# main.net
KiCad netlist of a schematic drawn in EAGLE
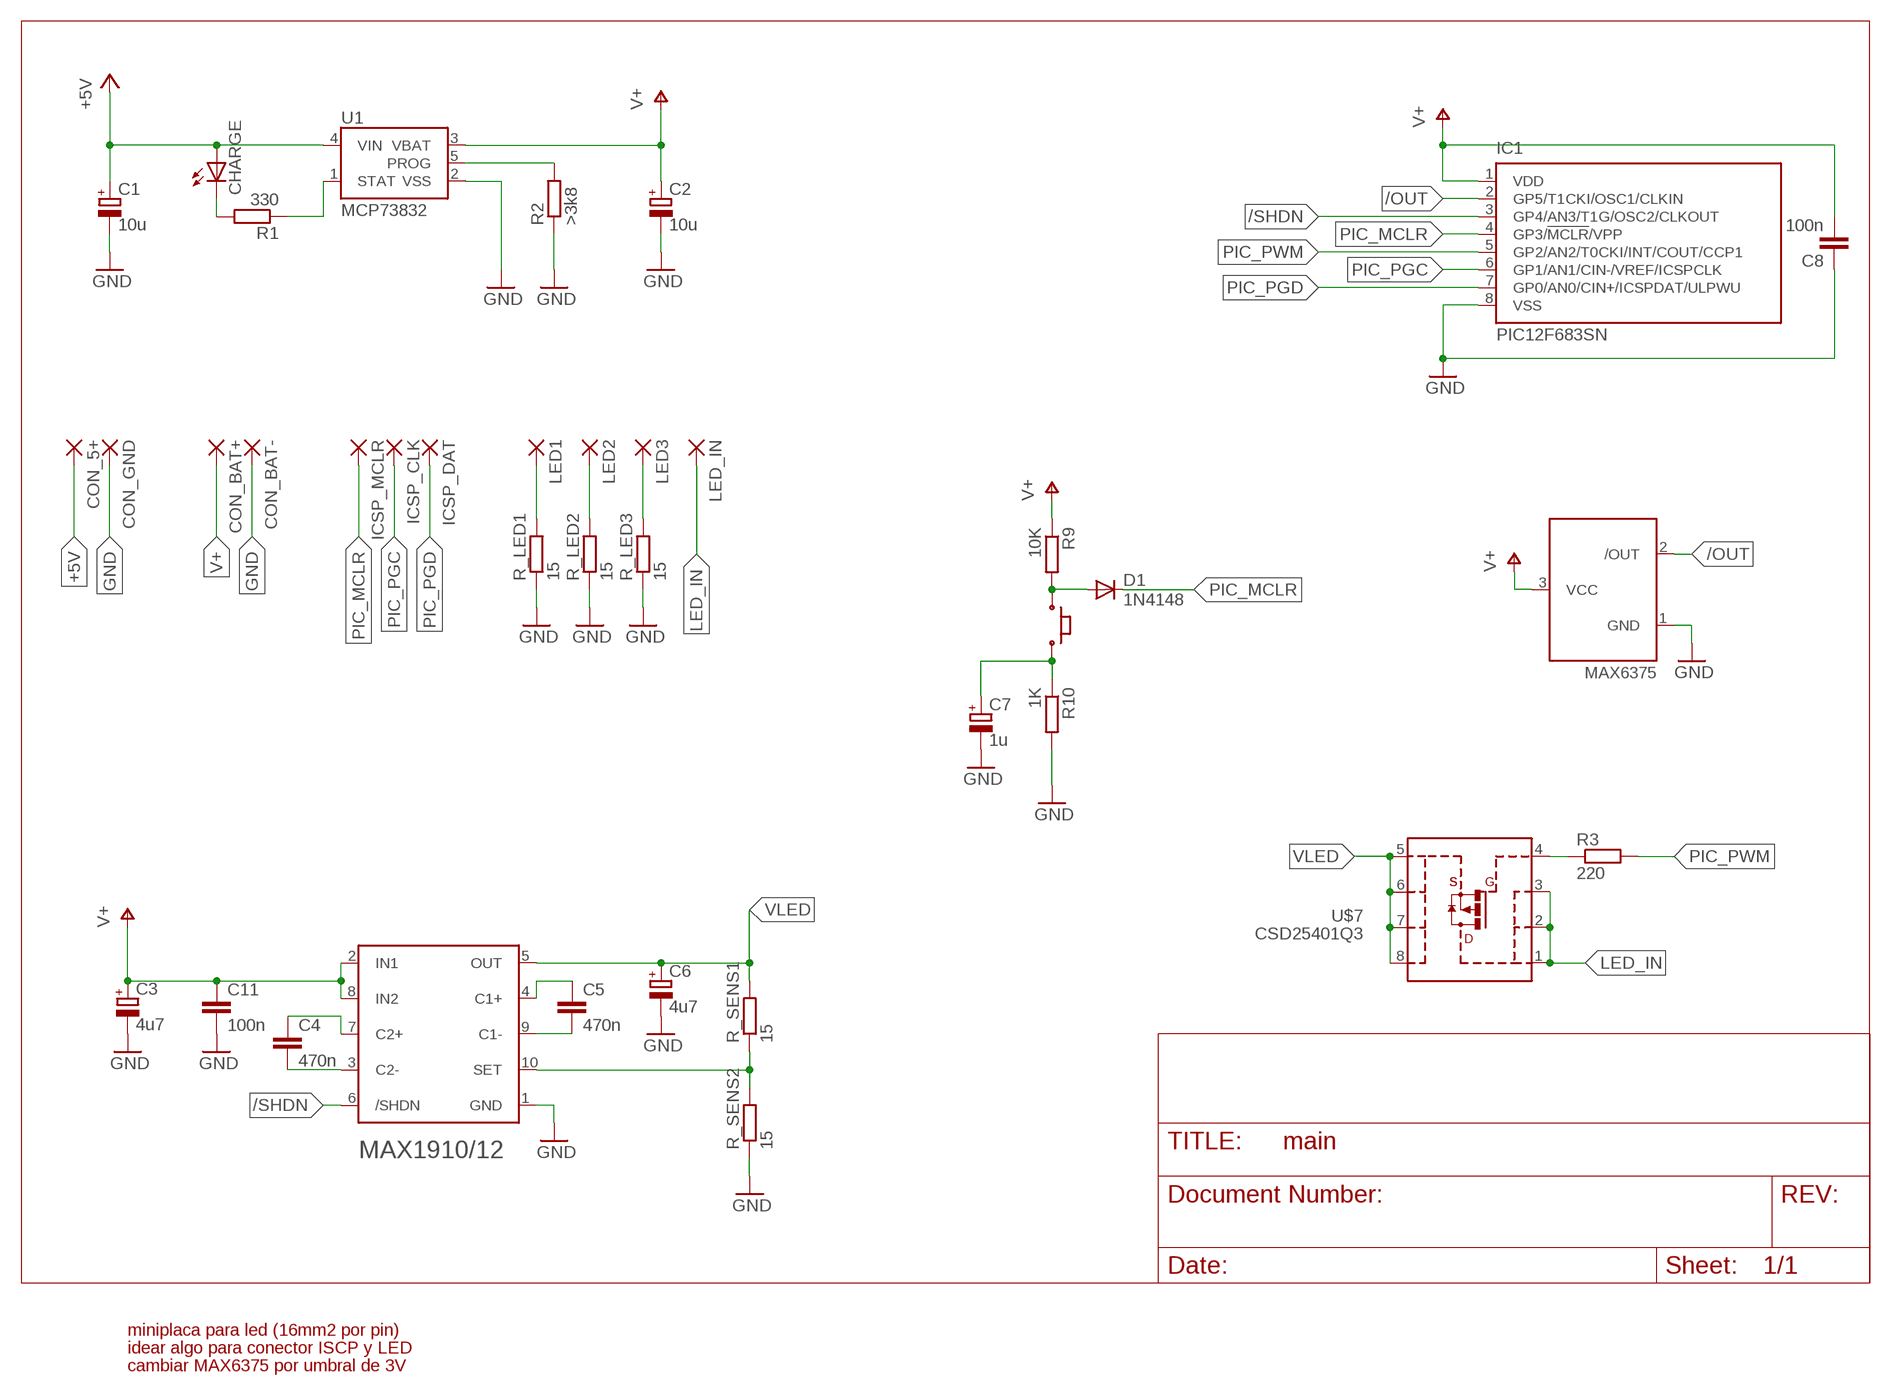
[diagram p0: schematic, sheet 1]

(export (version "E")
  (design (tool "Eeschema 10.0.6"))
  (components
    (comp (ref "C1")
      (value "10u")
      (footprint "eagle-import:SMC_A")
      (libsource (lib "eagle-import") (part "CPOL-EUSMCA"))
    )
    (comp (ref "C2")
      (value "10u")
      (footprint "eagle-import:SMC_A")
      (libsource (lib "eagle-import") (part "CPOL-EUSMCA"))
    )
    (comp (ref "C3")
      (value "4u7")
      (footprint "eagle-import:SMC_A")
      (libsource (lib "eagle-import") (part "CPOL-EUSMCA"))
    )
    (comp (ref "C4")
      (value "470n")
      (footprint "eagle-import:C1206")
      (libsource (lib "eagle-import") (part "C-EUC1206"))
    )
    (comp (ref "C5")
      (value "470n")
      (footprint "eagle-import:C1206")
      (libsource (lib "eagle-import") (part "C-EUC1206"))
    )
    (comp (ref "C6")
      (value "4u7")
      (footprint "eagle-import:SMC_A")
      (libsource (lib "eagle-import") (part "CPOL-EUSMCA"))
    )
    (comp (ref "C7")
      (value "1u")
      (footprint "eagle-import:SMC_A")
      (libsource (lib "eagle-import") (part "CPOL-EUSMCA"))
    )
    (comp (ref "C8")
      (value "100n")
      (footprint "eagle-import:C1206")
      (libsource (lib "eagle-import") (part "C-EUC1206"))
    )
    (comp (ref "C11")
      (value "100n")
      (footprint "eagle-import:C1206")
      (libsource (lib "eagle-import") (part "C-EUC1206"))
    )
    (comp (ref "CHARGE")
      (value "LEDCHIPLED_1206")
      (footprint "eagle-import:CHIPLED_1206")
      (libsource (lib "eagle-import") (part "LEDCHIPLED_1206"))
    )
    (comp (ref "CON_5+")
      (value "SMD5")
      (footprint "eagle-import:SMD2,54-5,08")
      (libsource (lib "eagle-import") (part "SMD5"))
    )
    (comp (ref "CON_BAT+")
      (value "SMD5")
      (footprint "eagle-import:SMD2,54-5,08")
      (libsource (lib "eagle-import") (part "SMD5"))
    )
    (comp (ref "CON_BAT-")
      (value "SMD5")
      (footprint "eagle-import:SMD2,54-5,08")
      (libsource (lib "eagle-import") (part "SMD5"))
    )
    (comp (ref "CON_GND")
      (value "SMD5")
      (footprint "eagle-import:SMD2,54-5,08")
      (libsource (lib "eagle-import") (part "SMD5"))
    )
    (comp (ref "D1")
      (value "1N4148")
      (footprint "eagle-import:SOD80")
      (libsource (lib "eagle-import") (part "1N4148"))
    )
    (comp (ref "IC1")
      (value "PIC12F683SN")
      (footprint "eagle-import:SO-08")
      (fields (field (name "MF") "MICROCHIP") (field (name "MPN") "PIC12F683-I/SN"))
      (libsource (lib "eagle-import") (part "PIC12F683SN"))
    )
    (comp (ref "ICSP_CLK")
      (value "SMD5")
      (footprint "eagle-import:SMD2,54-5,08")
      (libsource (lib "eagle-import") (part "SMD5"))
    )
    (comp (ref "ICSP_DAT")
      (value "SMD5")
      (footprint "eagle-import:SMD2,54-5,08")
      (libsource (lib "eagle-import") (part "SMD5"))
    )
    (comp (ref "ICSP_MCLR")
      (value "SMD5")
      (footprint "eagle-import:SMD2,54-5,08")
      (libsource (lib "eagle-import") (part "SMD5"))
    )
    (comp (ref "LED1")
      (value "SMD5")
      (footprint "eagle-import:SMD2,54-5,08")
      (libsource (lib "eagle-import") (part "SMD5"))
    )
    (comp (ref "LED2")
      (value "SMD5")
      (footprint "eagle-import:SMD2,54-5,08")
      (libsource (lib "eagle-import") (part "SMD5"))
    )
    (comp (ref "LED3")
      (value "SMD5")
      (footprint "eagle-import:SMD2,54-5,08")
      (libsource (lib "eagle-import") (part "SMD5"))
    )
    (comp (ref "LED_IN")
      (value "SMD5")
      (footprint "eagle-import:SMD2,54-5,08")
      (libsource (lib "eagle-import") (part "SMD5"))
    )
    (comp (ref "R1")
      (value "330")
      (footprint "eagle-import:R1206")
      (libsource (lib "eagle-import") (part "R-EU_R1206"))
    )
    (comp (ref "R2")
      (value ">3k8")
      (footprint "eagle-import:R1206")
      (libsource (lib "eagle-import") (part "R-EU_R1206"))
    )
    (comp (ref "R3")
      (value "220")
      (footprint "eagle-import:R1206")
      (libsource (lib "eagle-import") (part "R-EU_R1206"))
    )
    (comp (ref "R9")
      (value "10K")
      (footprint "eagle-import:R1206")
      (libsource (lib "eagle-import") (part "R-EU_R1206"))
    )
    (comp (ref "R10")
      (value "1K")
      (footprint "eagle-import:R1206")
      (libsource (lib "eagle-import") (part "R-EU_R1206"))
    )
    (comp (ref "R_LED1")
      (value "15")
      (footprint "eagle-import:R1206")
      (libsource (lib "eagle-import") (part "R-EU_R1206"))
    )
    (comp (ref "R_LED2")
      (value "15")
      (footprint "eagle-import:R1206")
      (libsource (lib "eagle-import") (part "R-EU_R1206"))
    )
    (comp (ref "R_LED3")
      (value "15")
      (footprint "eagle-import:R1206")
      (libsource (lib "eagle-import") (part "R-EU_R1206"))
    )
    (comp (ref "R_SENS1")
      (value "15")
      (footprint "eagle-import:R1206")
      (libsource (lib "eagle-import") (part "R-EU_R1206"))
    )
    (comp (ref "R_SENS2")
      (value "15")
      (footprint "eagle-import:R1206")
      (libsource (lib "eagle-import") (part "R-EU_R1206"))
    )
    (comp (ref "U$1")
      (value "MAX1910/12")
      (footprint "eagle-import:UMAX_USOP_10L")
      (libsource (lib "eagle-import") (part "MAX1910/12"))
    )
    (comp (ref "U$2")
      (value "MAX6375")
      (footprint "eagle-import:SC70-3-W")
      (libsource (lib "eagle-import") (part "MAX6375"))
    )
    (comp (ref "U$6")
      (value "MICROBUTTONE-MERCHAN")
      (footprint "eagle-import:MICROBUTTON_2")
      (libsource (lib "eagle-import") (part "MICROBUTTONE-MERCHAN"))
    )
    (comp (ref "U$7")
      (value "CSD25401Q3")
      (footprint "eagle-import:SON3X3")
      (libsource (lib "eagle-import") (part "CSD25401Q3"))
    )
    (comp (ref "U1")
      (value "MCP73832")
      (footprint "eagle-import:SOT23-5")
      (libsource (lib "eagle-import") (part "MCP73832"))
    )
  )
  (nets
    (net (code "1") (name "+5V") (class "Default")
      (node (ref "C1") (pin "+") (pinfunction "+_+") (pintype "passive"))
      (node (ref "CHARGE") (pin "A") (pinfunction "A_A") (pintype "passive"))
      (node (ref "CON_5+") (pin "1") (pinfunction "P_1") (pintype "passive"))
      (node (ref "U1") (pin "4") (pinfunction "VIN_4") (pintype "power_in"))
    )
    (net (code "2") (name "GND") (class "Default")
      (node (ref "C1") (pin "-") (pinfunction "-_-") (pintype "passive"))
      (node (ref "C11") (pin "2") (pinfunction "2_2") (pintype "passive"))
      (node (ref "C2") (pin "-") (pinfunction "-_-") (pintype "passive"))
      (node (ref "C3") (pin "-") (pinfunction "-_-") (pintype "passive"))
      (node (ref "C6") (pin "-") (pinfunction "-_-") (pintype "passive"))
      (node (ref "C7") (pin "-") (pinfunction "-_-") (pintype "passive"))
      (node (ref "C8") (pin "1") (pinfunction "1_1") (pintype "passive"))
      (node (ref "CON_BAT-") (pin "1") (pinfunction "P_1") (pintype "passive"))
      (node (ref "CON_GND") (pin "1") (pinfunction "P_1") (pintype "passive"))
      (node (ref "IC1") (pin "8") (pinfunction "VSS_8") (pintype "power_in"))
      (node (ref "R10") (pin "2") (pinfunction "2_2") (pintype "passive"))
      (node (ref "R2") (pin "1") (pinfunction "1_1") (pintype "passive"))
      (node (ref "R_LED1") (pin "1") (pinfunction "1_1") (pintype "passive"))
      (node (ref "R_LED2") (pin "1") (pinfunction "1_1") (pintype "passive"))
      (node (ref "R_LED3") (pin "1") (pinfunction "1_1") (pintype "passive"))
      (node (ref "R_SENS2") (pin "1") (pinfunction "1_1") (pintype "passive"))
      (node (ref "U$1") (pin "1") (pinfunction "GND_1") (pintype "power_in"))
      (node (ref "U$2") (pin "1") (pinfunction "GND_1") (pintype "power_in"))
      (node (ref "U1") (pin "2") (pinfunction "VSS_2") (pintype "power_in"))
    )
    (net (code "3") (name "LED_IN") (class "Default")
      (node (ref "LED_IN") (pin "1") (pinfunction "P_1") (pintype "passive"))
      (node (ref "U$7") (pin "1") (pinfunction "D$1_1") (pintype "bidirectional"))
      (node (ref "U$7") (pin "2") (pinfunction "D$2_2") (pintype "bidirectional"))
      (node (ref "U$7") (pin "3") (pinfunction "D$3_3") (pintype "bidirectional"))
    )
    (net (code "4") (name "Net-(C7-Pad+)") (class "Default")
      (node (ref "C7") (pin "+") (pinfunction "+_+") (pintype "passive"))
      (node (ref "R10") (pin "1") (pinfunction "1_1") (pintype "passive"))
      (node (ref "U$6") (pin "P$2") (pinfunction "P$2_P$2") (pintype "bidirectional"))
    )
    (net (code "5") (name "Net-(CHARGE-PadC)") (class "Default")
      (node (ref "CHARGE") (pin "C") (pinfunction "C_C") (pintype "passive"))
      (node (ref "R1") (pin "2") (pinfunction "2_2") (pintype "passive"))
    )
    (net (code "6") (name "Net-(D1-A)") (class "Default")
      (node (ref "D1") (pin "1") (pinfunction "A_1") (pintype "passive"))
      (node (ref "R9") (pin "2") (pinfunction "2_2") (pintype "passive"))
      (node (ref "U$6") (pin "P$1") (pinfunction "P$1_P$1") (pintype "bidirectional"))
    )
    (net (code "7") (name "Net-(LED1-P)") (class "Default")
      (node (ref "LED1") (pin "1") (pinfunction "P_1") (pintype "passive"))
      (node (ref "R_LED1") (pin "2") (pinfunction "2_2") (pintype "passive"))
    )
    (net (code "8") (name "Net-(LED2-P)") (class "Default")
      (node (ref "LED2") (pin "1") (pinfunction "P_1") (pintype "passive"))
      (node (ref "R_LED2") (pin "2") (pinfunction "2_2") (pintype "passive"))
    )
    (net (code "9") (name "Net-(LED3-P)") (class "Default")
      (node (ref "LED3") (pin "1") (pinfunction "P_1") (pintype "passive"))
      (node (ref "R_LED3") (pin "2") (pinfunction "2_2") (pintype "passive"))
    )
    (net (code "10") (name "Net-(U$1-C1+)") (class "Default")
      (node (ref "C5") (pin "1") (pinfunction "1_1") (pintype "passive"))
      (node (ref "U$1") (pin "4") (pinfunction "C1+_4") (pintype "bidirectional"))
    )
    (net (code "11") (name "Net-(U$1-C1-)") (class "Default")
      (node (ref "C5") (pin "2") (pinfunction "2_2") (pintype "passive"))
      (node (ref "U$1") (pin "9") (pinfunction "C1-_9") (pintype "bidirectional"))
    )
    (net (code "12") (name "Net-(U$1-C2+)") (class "Default")
      (node (ref "C4") (pin "1") (pinfunction "1_1") (pintype "passive"))
      (node (ref "U$1") (pin "7") (pinfunction "C2+_7") (pintype "bidirectional"))
    )
    (net (code "13") (name "Net-(U$1-C2-)") (class "Default")
      (node (ref "C4") (pin "2") (pinfunction "2_2") (pintype "passive"))
      (node (ref "U$1") (pin "3") (pinfunction "C2-_3") (pintype "bidirectional"))
    )
    (net (code "14") (name "Net-(U$1-SET)") (class "Default")
      (node (ref "R_SENS1") (pin "1") (pinfunction "1_1") (pintype "passive"))
      (node (ref "R_SENS2") (pin "2") (pinfunction "2_2") (pintype "passive"))
      (node (ref "U$1") (pin "10") (pinfunction "SET_10") (pintype "input"))
    )
    (net (code "15") (name "Net-(U$7-G$4)") (class "Default")
      (node (ref "R3") (pin "1") (pinfunction "1_1") (pintype "passive"))
      (node (ref "U$7") (pin "4") (pinfunction "G$4_4") (pintype "bidirectional"))
    )
    (net (code "16") (name "Net-(U1-PROG)") (class "Default")
      (node (ref "R2") (pin "2") (pinfunction "2_2") (pintype "passive"))
      (node (ref "U1") (pin "5") (pinfunction "PROG_5") (pintype "input"))
    )
    (net (code "17") (name "Net-(U1-STAT)") (class "Default")
      (node (ref "R1") (pin "1") (pinfunction "1_1") (pintype "passive"))
      (node (ref "U1") (pin "1") (pinfunction "STAT_1") (pintype "output"))
    )
    (net (code "18") (name "PIC_MCLR") (class "Default")
      (node (ref "D1") (pin "2") (pinfunction "C_2") (pintype "passive"))
      (node (ref "IC1") (pin "4") (pinfunction "GP3/~{MCLR}/VPP_4") (pintype "bidirectional"))
      (node (ref "ICSP_MCLR") (pin "1") (pinfunction "P_1") (pintype "passive"))
    )
    (net (code "19") (name "PIC_PGC") (class "Default")
      (node (ref "IC1") (pin "6") (pinfunction "GP1/AN1/CIN-/VREF/ICSPCLK_6") (pintype "bidirectional"))
      (node (ref "ICSP_CLK") (pin "1") (pinfunction "P_1") (pintype "passive"))
    )
    (net (code "20") (name "PIC_PGD") (class "Default")
      (node (ref "IC1") (pin "7") (pinfunction "GP0/AN0/CIN+/ICSPDAT/ULPWU_7") (pintype "bidirectional"))
      (node (ref "ICSP_DAT") (pin "1") (pinfunction "P_1") (pintype "passive"))
    )
    (net (code "21") (name "PIC_PWM") (class "Default")
      (node (ref "IC1") (pin "5") (pinfunction "GP2/AN2/T0CKI/INT/COUT/CCP1_5") (pintype "bidirectional"))
      (node (ref "R3") (pin "2") (pinfunction "2_2") (pintype "passive"))
    )
    (net (code "22") (name "V+") (class "Default")
      (node (ref "C11") (pin "1") (pinfunction "1_1") (pintype "passive"))
      (node (ref "C2") (pin "+") (pinfunction "+_+") (pintype "passive"))
      (node (ref "C3") (pin "+") (pinfunction "+_+") (pintype "passive"))
      (node (ref "C8") (pin "2") (pinfunction "2_2") (pintype "passive"))
      (node (ref "CON_BAT+") (pin "1") (pinfunction "P_1") (pintype "passive"))
      (node (ref "IC1") (pin "1") (pinfunction "VDD_1") (pintype "power_in"))
      (node (ref "R9") (pin "1") (pinfunction "1_1") (pintype "passive"))
      (node (ref "U$1") (pin "2") (pinfunction "IN1_2") (pintype "power_in"))
      (node (ref "U$1") (pin "8") (pinfunction "IN2_8") (pintype "power_in"))
      (node (ref "U$2") (pin "3") (pinfunction "VCC_3") (pintype "power_in"))
      (node (ref "U1") (pin "3") (pinfunction "VBAT_3") (pintype "power_in"))
    )
    (net (code "23") (name "VLED") (class "Default")
      (node (ref "C6") (pin "+") (pinfunction "+_+") (pintype "passive"))
      (node (ref "R_SENS1") (pin "2") (pinfunction "2_2") (pintype "passive"))
      (node (ref "U$1") (pin "5") (pinfunction "OUT_5") (pintype "output"))
      (node (ref "U$7") (pin "5") (pinfunction "S$5_5") (pintype "bidirectional"))
      (node (ref "U$7") (pin "6") (pinfunction "S$6_6") (pintype "bidirectional"))
      (node (ref "U$7") (pin "7") (pinfunction "S$7_7") (pintype "bidirectional"))
      (node (ref "U$7") (pin "8") (pinfunction "S$8_8") (pintype "bidirectional"))
    )
    (net (code "24") (name "{slash}OUT") (class "Default")
      (node (ref "IC1") (pin "2") (pinfunction "GP5/T1CKI/OSC1/CLKIN_2") (pintype "bidirectional"))
      (node (ref "U$2") (pin "2") (pinfunction "/OUT_2") (pintype "output"))
    )
    (net (code "25") (name "{slash}SHDN") (class "Default")
      (node (ref "IC1") (pin "3") (pinfunction "GP4/AN3/T1G/OSC2/CLKOUT_3") (pintype "bidirectional"))
      (node (ref "U$1") (pin "6") (pinfunction "/SHDN_6") (pintype "bidirectional"))
    )
  )
)
